# sensors_l.net
KiCad netlist of a schematic drawn in EAGLE
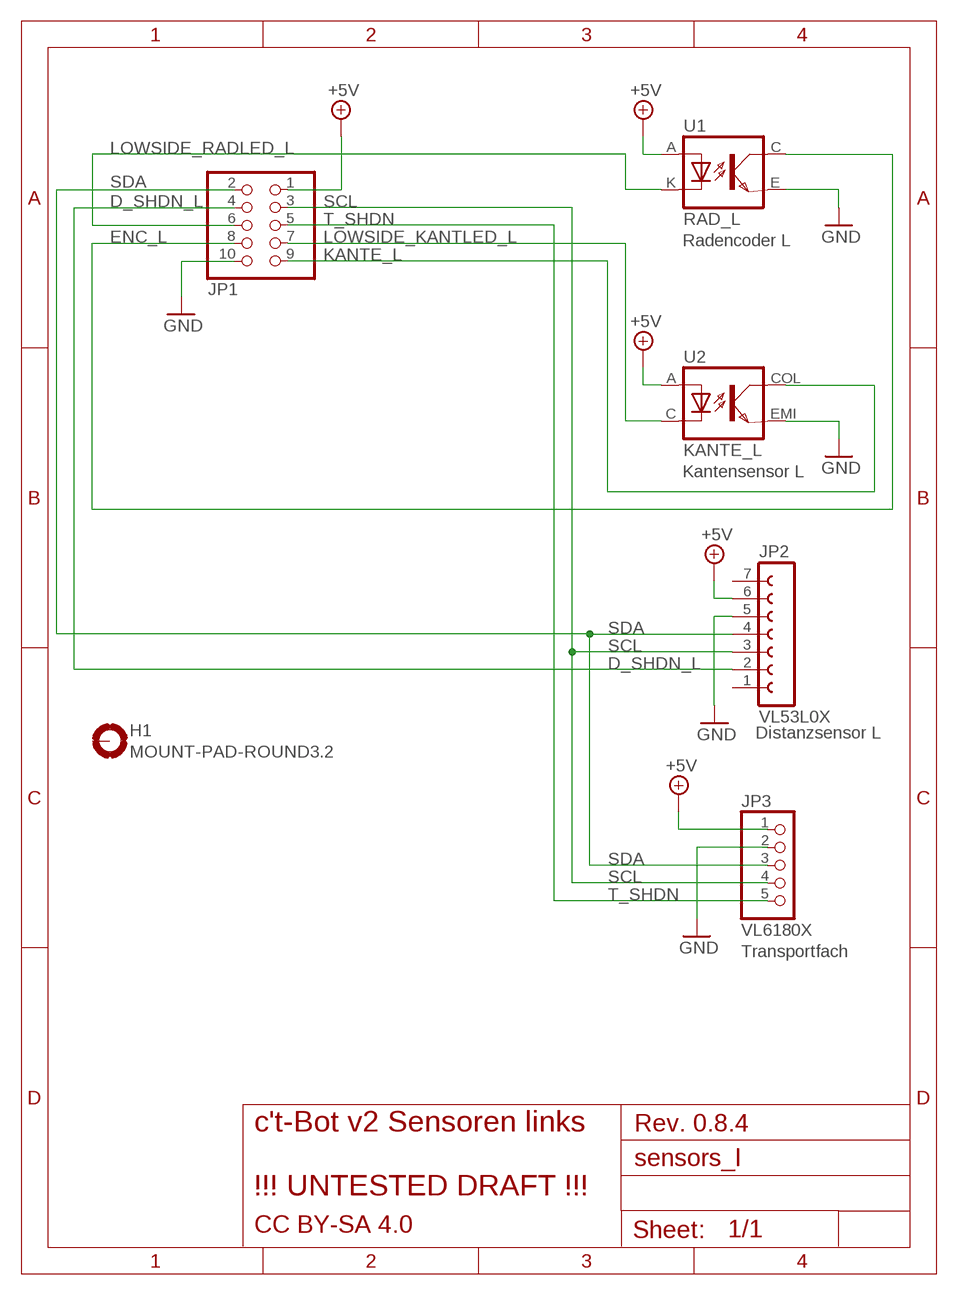
[diagram p0: schematic, sheet 1]

(export (version "E")
  (design (tool "Eeschema 10.0.6"))
  (components
    (comp (ref "H1")
      (value "MOUNT-PAD-ROUND3.2")
      (footprint "eagle-import:3,2-PAD")
      (libsource (lib "eagle-import") (part "MOUNT-PAD-ROUND3.2"))
    )
    (comp (ref "JP1")
      (value "PINHD-2X5")
      (footprint "eagle-import:2X05")
      (libsource (lib "eagle-import") (part "PINHD-2X5"))
    )
    (comp (ref "JP2")
      (value "VL53L0X")
      (footprint "eagle-import:FE07W")
      (libsource (lib "eagle-import") (part "FE07W"))
    )
    (comp (ref "JP3")
      (value "VL6180X")
      (footprint "eagle-import:1X05")
      (libsource (lib "eagle-import") (part "PINHD-1X5"))
    )
    (comp (ref "U1")
      (value "RAD_L")
      (footprint "eagle-import:4")
      (libsource (lib "eagle-import") (part "CNY70DEF"))
    )
    (comp (ref "U2")
      (value "KANTE_L")
      (footprint "eagle-import:EDGE")
      (libsource (lib "eagle-import") (part "CNY70"))
    )
  )
  (nets
    (net (code "1") (name "+5V") (class "Default")
      (node (ref "JP1") (pin "1") (pinfunction "1_1") (pintype "passive"))
      (node (ref "JP2") (pin "6") (pinfunction "6_6") (pintype "passive"))
      (node (ref "JP3") (pin "1") (pinfunction "1_1") (pintype "passive"))
      (node (ref "U1") (pin "A") (pinfunction "A_A") (pintype "passive"))
      (node (ref "U2") (pin "A") (pinfunction "A_A") (pintype "passive"))
    )
    (net (code "2") (name "/D_SHDN_L") (class "Default")
      (node (ref "JP1") (pin "4") (pinfunction "4_4") (pintype "passive"))
      (node (ref "JP2") (pin "2") (pinfunction "2_2") (pintype "passive"))
    )
    (net (code "3") (name "/ENC_L") (class "Default")
      (node (ref "JP1") (pin "8") (pinfunction "8_8") (pintype "passive"))
      (node (ref "U1") (pin "C") (pinfunction "COL_C") (pintype "passive"))
    )
    (net (code "4") (name "/KANTE_L") (class "Default")
      (node (ref "JP1") (pin "9") (pinfunction "9_9") (pintype "passive"))
      (node (ref "U2") (pin "COL") (pinfunction "COL_COL") (pintype "passive"))
    )
    (net (code "5") (name "/LOWSIDE_KANTLED_L") (class "Default")
      (node (ref "JP1") (pin "7") (pinfunction "7_7") (pintype "passive"))
      (node (ref "U2") (pin "C") (pinfunction "C_C") (pintype "passive"))
    )
    (net (code "6") (name "/LOWSIDE_RADLED_L") (class "Default")
      (node (ref "JP1") (pin "6") (pinfunction "6_6") (pintype "passive"))
      (node (ref "U1") (pin "K") (pinfunction "C_K") (pintype "passive"))
    )
    (net (code "7") (name "/SCL") (class "Default")
      (node (ref "JP1") (pin "3") (pinfunction "3_3") (pintype "passive"))
      (node (ref "JP2") (pin "3") (pinfunction "3_3") (pintype "passive"))
      (node (ref "JP3") (pin "4") (pinfunction "4_4") (pintype "passive"))
    )
    (net (code "8") (name "/SDA") (class "Default")
      (node (ref "JP1") (pin "2") (pinfunction "2_2") (pintype "passive"))
      (node (ref "JP2") (pin "4") (pinfunction "4_4") (pintype "passive"))
      (node (ref "JP3") (pin "3") (pinfunction "3_3") (pintype "passive"))
    )
    (net (code "9") (name "/T_SHDN") (class "Default")
      (node (ref "JP1") (pin "5") (pinfunction "5_5") (pintype "passive"))
      (node (ref "JP3") (pin "5") (pinfunction "5_5") (pintype "passive"))
    )
    (net (code "10") (name "GND") (class "Default")
      (node (ref "JP1") (pin "10") (pinfunction "10_10") (pintype "passive"))
      (node (ref "JP2") (pin "5") (pinfunction "5_5") (pintype "passive"))
      (node (ref "JP3") (pin "2") (pinfunction "2_2") (pintype "passive"))
      (node (ref "U1") (pin "E") (pinfunction "EMI_E") (pintype "passive"))
      (node (ref "U2") (pin "EMI") (pinfunction "EMI_EMI") (pintype "passive"))
    )
    (net (code "11") (name "unconnected-(H1-MOUNT-PadB3,2)") (class "Default")
      (node (ref "H1") (pin "B3,2") (pinfunction "MOUNT_B3,2") (pintype "passive"))
    )
    (net (code "12") (name "unconnected-(JP2-Pad1)") (class "Default")
      (node (ref "JP2") (pin "1") (pinfunction "1_1") (pintype "passive"))
    )
    (net (code "13") (name "unconnected-(JP2-Pad7)") (class "Default")
      (node (ref "JP2") (pin "7") (pinfunction "7_7") (pintype "passive"))
    )
  )
)
